# MCU.net
KiCad netlist of a schematic drawn in Altium Designer
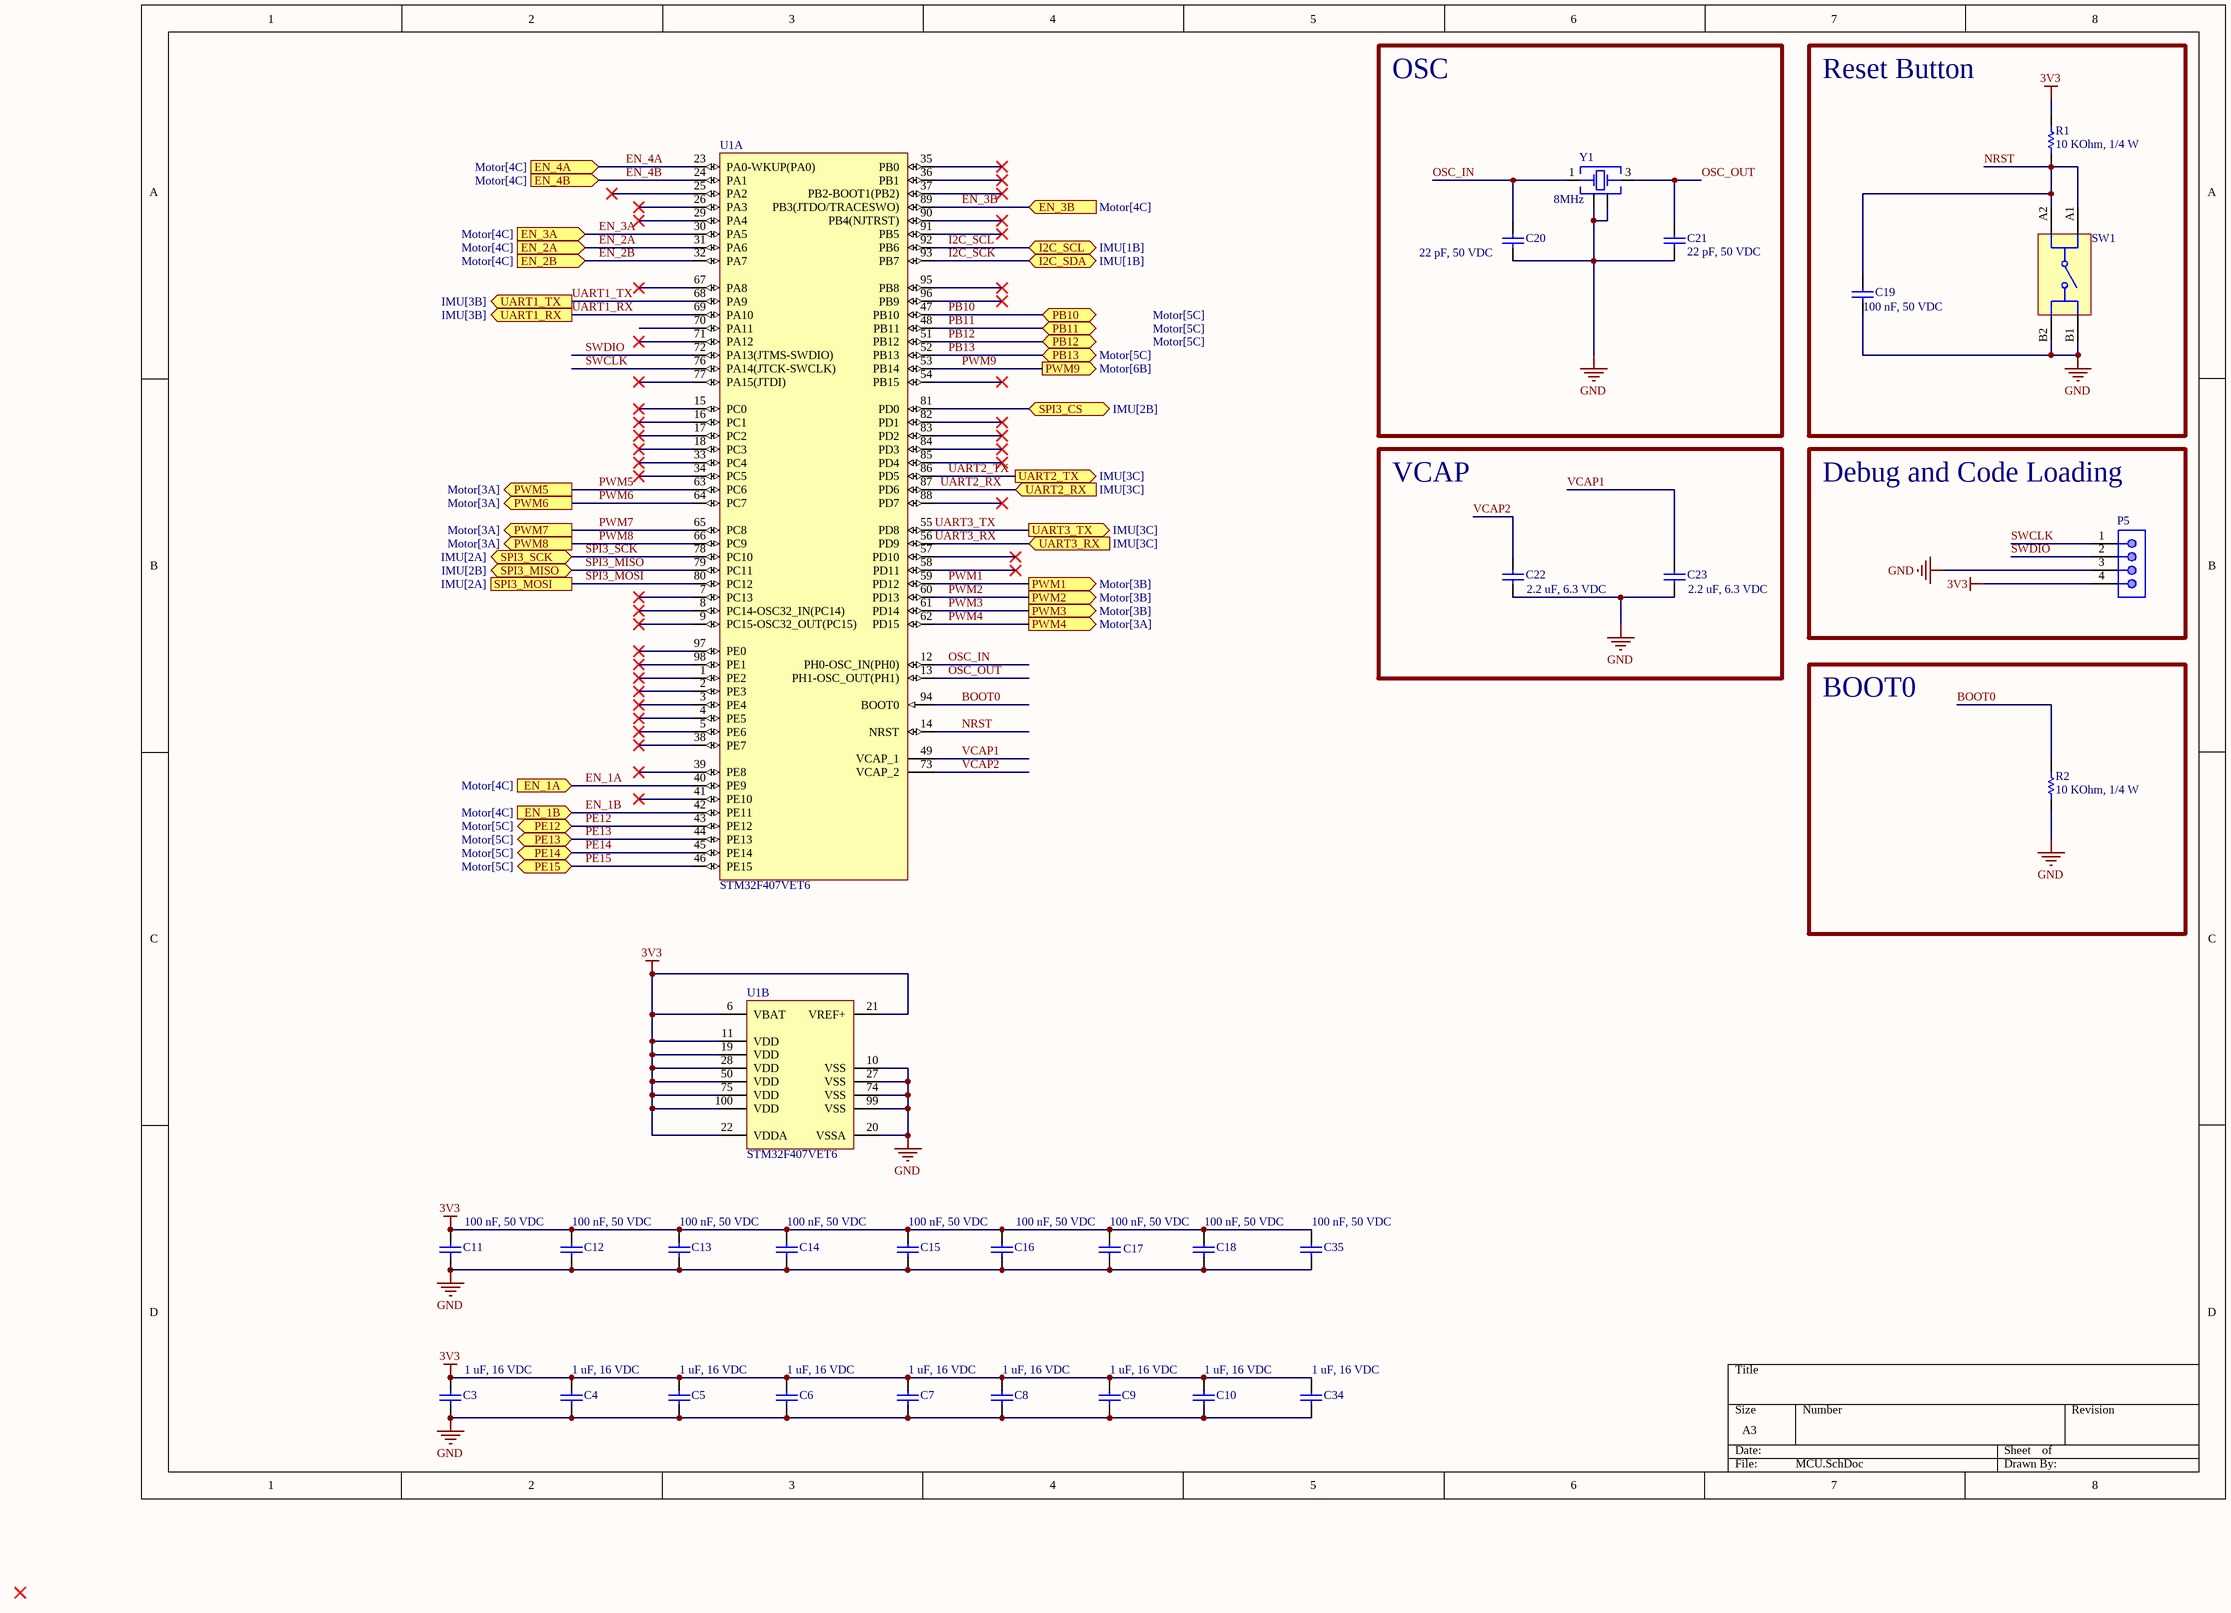
[diagram p0: MCU.SchDoc]

(export (version "E")
  (design (tool "Eeschema 10.0.6"))
  (components
    (comp (ref "C3")
      (value "1 uF, 16 VDC")
      (footprint "CAP_0603")
      (description "CAP, size 0603, 1 uF, 16 VDC")
      (fields (field (name "TOLERANCE") "+/-10%"))
      (libsource (lib "Altium_Ceramic_Cap") (part "0106031051016"))
    )
    (comp (ref "C4")
      (value "1 uF, 16 VDC")
      (footprint "CAP_0603")
      (description "CAP, size 0603, 1 uF, 16 VDC")
      (fields (field (name "TOLERANCE") "+/-10%"))
      (libsource (lib "Altium_Ceramic_Cap") (part "0106031051016"))
    )
    (comp (ref "C5")
      (value "1 uF, 16 VDC")
      (footprint "CAP_0603")
      (description "CAP, size 0603, 1 uF, 16 VDC")
      (fields (field (name "TOLERANCE") "+/-10%"))
      (libsource (lib "Altium_Ceramic_Cap") (part "0106031051016"))
    )
    (comp (ref "C6")
      (value "1 uF, 16 VDC")
      (footprint "CAP_0603")
      (description "CAP, size 0603, 1 uF, 16 VDC")
      (fields (field (name "TOLERANCE") "+/-10%"))
      (libsource (lib "Altium_Ceramic_Cap") (part "0106031051016"))
    )
    (comp (ref "C7")
      (value "1 uF, 16 VDC")
      (footprint "CAP_0603")
      (description "CAP, size 0603, 1 uF, 16 VDC")
      (fields (field (name "TOLERANCE") "+/-10%"))
      (libsource (lib "Altium_Ceramic_Cap") (part "0106031051016"))
    )
    (comp (ref "C8")
      (value "1 uF, 16 VDC")
      (footprint "CAP_0603")
      (description "CAP, size 0603, 1 uF, 16 VDC")
      (fields (field (name "TOLERANCE") "+/-10%"))
      (libsource (lib "Altium_Ceramic_Cap") (part "0106031051016"))
    )
    (comp (ref "C9")
      (value "1 uF, 16 VDC")
      (footprint "CAP_0603")
      (description "CAP, size 0603, 1 uF, 16 VDC")
      (fields (field (name "TOLERANCE") "+/-10%"))
      (libsource (lib "Altium_Ceramic_Cap") (part "0106031051016"))
    )
    (comp (ref "C10")
      (value "1 uF, 16 VDC")
      (footprint "CAP_0603")
      (description "CAP, size 0603, 1 uF, 16 VDC")
      (fields (field (name "TOLERANCE") "+/-10%"))
      (libsource (lib "Altium_Ceramic_Cap") (part "0106031051016"))
    )
    (comp (ref "C11")
      (value "100 nF, 50 VDC")
      (footprint "CAP_0603")
      (description "CAP, size 0603, 100 nF, 50 VDC")
      (fields (field (name "TOLERANCE") "+/-10%"))
      (libsource (lib "Altium_Ceramic_Cap") (part "0106031041050"))
    )
    (comp (ref "C12")
      (value "100 nF, 50 VDC")
      (footprint "CAP_0603")
      (description "CAP, size 0603, 100 nF, 50 VDC")
      (fields (field (name "TOLERANCE") "+/-10%"))
      (libsource (lib "Altium_Ceramic_Cap") (part "0106031041050"))
    )
    (comp (ref "C13")
      (value "100 nF, 50 VDC")
      (footprint "CAP_0603")
      (description "CAP, size 0603, 100 nF, 50 VDC")
      (fields (field (name "TOLERANCE") "+/-10%"))
      (libsource (lib "Altium_Ceramic_Cap") (part "0106031041050"))
    )
    (comp (ref "C14")
      (value "100 nF, 50 VDC")
      (footprint "CAP_0603")
      (description "CAP, size 0603, 100 nF, 50 VDC")
      (fields (field (name "TOLERANCE") "+/-10%"))
      (libsource (lib "Altium_Ceramic_Cap") (part "0106031041050"))
    )
    (comp (ref "C15")
      (value "100 nF, 50 VDC")
      (footprint "CAP_0603")
      (description "CAP, size 0603, 100 nF, 50 VDC")
      (fields (field (name "TOLERANCE") "+/-10%"))
      (libsource (lib "Altium_Ceramic_Cap") (part "0106031041050"))
    )
    (comp (ref "C16")
      (value "100 nF, 50 VDC")
      (footprint "CAP_0603")
      (description "CAP, size 0603, 100 nF, 50 VDC")
      (fields (field (name "TOLERANCE") "+/-10%"))
      (libsource (lib "Altium_Ceramic_Cap") (part "0106031041050"))
    )
    (comp (ref "C17")
      (value "100 nF, 50 VDC")
      (footprint "CAP_0603")
      (description "CAP, size 0603, 100 nF, 50 VDC")
      (fields (field (name "TOLERANCE") "+/-10%"))
      (libsource (lib "Altium_Ceramic_Cap") (part "0106031041050"))
    )
    (comp (ref "C18")
      (value "100 nF, 50 VDC")
      (footprint "CAP_0603")
      (description "CAP, size 0603, 100 nF, 50 VDC")
      (fields (field (name "TOLERANCE") "+/-10%"))
      (libsource (lib "Altium_Ceramic_Cap") (part "0106031041050"))
    )
    (comp (ref "C19")
      (value "100 nF, 50 VDC")
      (footprint "CAP_0603")
      (description "CAP, size 0603, 100 nF, 50 VDC")
      (fields (field (name "TOLERANCE") "+/-10%"))
      (libsource (lib "Altium_Ceramic_Cap") (part "0106031041050"))
    )
    (comp (ref "C20")
      (value "22 pF, 50 VDC")
      (footprint "CAP_0603")
      (description "CAP, size 0603, 22 pF, 50 VDC")
      (fields (field (name "TOLERANCE") "+/-5%"))
      (libsource (lib "Altium_Ceramic_Cap") (part "0106032200550"))
    )
    (comp (ref "C21")
      (value "22 pF, 50 VDC")
      (footprint "CAP_0603")
      (description "CAP, size 0603, 22 pF, 50 VDC")
      (fields (field (name "TOLERANCE") "+/-5%"))
      (libsource (lib "Altium_Ceramic_Cap") (part "0106032200550"))
    )
    (comp (ref "C22")
      (value "2.2 uF, 6.3 VDC")
      (footprint "CAP_0603")
      (description "CAP, size 0603, 2.2 uF, 6.3 VDC")
      (fields (field (name "TOLERANCE") "+/-10%"))
      (libsource (lib "Altium_Ceramic_Cap") (part "010603225106.3"))
    )
    (comp (ref "C23")
      (value "2.2 uF, 6.3 VDC")
      (footprint "CAP_0603")
      (description "CAP, size 0603, 2.2 uF, 6.3 VDC")
      (fields (field (name "TOLERANCE") "+/-10%"))
      (libsource (lib "Altium_Ceramic_Cap") (part "010603225106.3"))
    )
    (comp (ref "C34")
      (value "1 uF, 16 VDC")
      (footprint "CAP_0603")
      (description "CAP, size 0603, 1 uF, 16 VDC")
      (fields (field (name "TOLERANCE") "+/-10%"))
      (libsource (lib "Altium_Ceramic_Cap") (part "0106031051016"))
    )
    (comp (ref "C35")
      (value "100 nF, 50 VDC")
      (footprint "CAP_0603")
      (description "CAP, size 0603, 100 nF, 50 VDC")
      (fields (field (name "TOLERANCE") "+/-10%"))
      (libsource (lib "Altium_Ceramic_Cap") (part "0106031041050"))
    )
    (comp (ref "P5")
      (value "61300411121")
      (footprint "61300411121")
      (description "WR-PHD Pin Header, THT, pitch 2.54mm, Single Row, Vertical, 4p")
      (fields (field (name "MANUFACTURER") "Wurth Elektronik"))
      (libsource (lib "Altium_Header") (part "61300411121"))
    )
    (comp (ref "R1")
      (value "10 KOhm, 1/4 W")
      (footprint "resistor_0603")
      (description "RES, size 0603, 10 KOhm, 1/4 W")
      (libsource (lib "Altium_Resistor") (part "0006031031"))
    )
    (comp (ref "R2")
      (value "10 KOhm, 1/4 W")
      (footprint "resistor_0603")
      (description "RES, size 0603, 10 KOhm, 1/4 W")
      (libsource (lib "Altium_Resistor") (part "0006031031"))
    )
    (comp (ref "SW1")
      (value "430483035816")
      (footprint "WS-TASV_L6W6H3.5_4304x30358x6")
      (description "WS-TASV J-Bend SMT Washable Tact Switch, 12VDC, 50mA, 160g, height 3.5mm")
      (fields (field (name "MANUFACTURER") "Wurth Elektronik"))
      (libsource (lib "Board_C24") (part "430483035816"))
    )
    (comp (ref "U1")
      (value "STM32F407VET6")
      (footprint "STM-LQFP100_V")
      (fields (field (name "MANUFACTURER") "STMicroelectronics"))
      (libsource (lib "Altium Content Vault") (part "MC-ARM-STM32F40X_41X-SQ100"))
    )
    (comp (ref "Y1")
      (value "8MHz")
      (footprint "WE-XTAL_CFPX-104")
      (description "WE-XTAL Quartz Crystal, SMT, CFPX-104, 8MHz, +/-20ppm")
      (fields
        (field (name "MANUFACTURER PART NUMBER") "830106162701")
        (field (name "MANUFACTURER") "Wurth Elektronik")
      )
      (libsource (lib "Board_C24") (part "830106162701"))
    )
  )
  (nets
    (net (code "1") (name "/BOOT0") (class "Default")
      (node (ref "R2") (pin "2") (pinfunction "2_2") (pintype "passive"))
      (node (ref "U1") (pin "94") (pinfunction "BOOT0_94") (pintype "input"))
    )
    (net (code "2") (name "/EN_1A") (class "Default")
      (node (ref "U1") (pin "40") (pinfunction "PE9_40") (pintype "bidirectional"))
    )
    (net (code "3") (name "/EN_1B") (class "Default")
      (node (ref "U1") (pin "42") (pinfunction "PE11_42") (pintype "bidirectional"))
    )
    (net (code "4") (name "/EN_2A") (class "Default")
      (node (ref "U1") (pin "31") (pinfunction "PA6_31") (pintype "bidirectional"))
    )
    (net (code "5") (name "/EN_2B") (class "Default")
      (node (ref "U1") (pin "32") (pinfunction "PA7_32") (pintype "bidirectional"))
    )
    (net (code "6") (name "/EN_3A") (class "Default")
      (node (ref "U1") (pin "30") (pinfunction "PA5_30") (pintype "bidirectional"))
    )
    (net (code "7") (name "/EN_3B") (class "Default")
      (node (ref "U1") (pin "89") (pinfunction "PB3(JTDO/TRACESWO)_89") (pintype "bidirectional"))
    )
    (net (code "8") (name "/EN_4A") (class "Default")
      (node (ref "U1") (pin "23") (pinfunction "PA0-WKUP(PA0)_23") (pintype "bidirectional"))
    )
    (net (code "9") (name "/EN_4B") (class "Default")
      (node (ref "U1") (pin "24") (pinfunction "PA1_24") (pintype "bidirectional"))
    )
    (net (code "10") (name "/I2C_SCK") (class "Default")
      (node (ref "U1") (pin "93") (pinfunction "PB7_93") (pintype "bidirectional"))
    )
    (net (code "11") (name "/I2C_SCL") (class "Default")
      (node (ref "U1") (pin "92") (pinfunction "PB6_92") (pintype "bidirectional"))
    )
    (net (code "12") (name "/NRST") (class "Default")
      (node (ref "C19") (pin "2") (pinfunction "2_2") (pintype "passive"))
      (node (ref "R1") (pin "1") (pinfunction "1_1") (pintype "passive"))
      (node (ref "SW1") (pin "A1") (pinfunction "A1_A1") (pintype "passive"))
      (node (ref "SW1") (pin "A2") (pinfunction "A2_A2") (pintype "passive"))
      (node (ref "U1") (pin "14") (pinfunction "NRST_14") (pintype "bidirectional"))
    )
    (net (code "13") (name "/OSC_IN") (class "Default")
      (node (ref "C20") (pin "2") (pinfunction "2_2") (pintype "passive"))
      (node (ref "U1") (pin "12") (pinfunction "PH0-OSC_IN(PH0)_12") (pintype "bidirectional"))
      (node (ref "Y1") (pin "1") (pinfunction "OSC1_1") (pintype "passive"))
    )
    (net (code "14") (name "/OSC_OUT") (class "Default")
      (node (ref "C21") (pin "2") (pinfunction "2_2") (pintype "passive"))
      (node (ref "U1") (pin "13") (pinfunction "PH1-OSC_OUT(PH1)_13") (pintype "bidirectional"))
      (node (ref "Y1") (pin "3") (pinfunction "OSC2_3") (pintype "passive"))
    )
    (net (code "15") (name "/PB10") (class "Default")
      (node (ref "U1") (pin "47") (pinfunction "PB10_47") (pintype "bidirectional"))
    )
    (net (code "16") (name "/PB11") (class "Default")
      (node (ref "U1") (pin "48") (pinfunction "PB11_48") (pintype "bidirectional"))
    )
    (net (code "17") (name "/PB12") (class "Default")
      (node (ref "U1") (pin "51") (pinfunction "PB12_51") (pintype "bidirectional"))
    )
    (net (code "18") (name "/PB13") (class "Default")
      (node (ref "U1") (pin "52") (pinfunction "PB13_52") (pintype "bidirectional"))
    )
    (net (code "19") (name "/PE12") (class "Default")
      (node (ref "U1") (pin "43") (pinfunction "PE12_43") (pintype "bidirectional"))
    )
    (net (code "20") (name "/PE13") (class "Default")
      (node (ref "U1") (pin "44") (pinfunction "PE13_44") (pintype "bidirectional"))
    )
    (net (code "21") (name "/PE14") (class "Default")
      (node (ref "U1") (pin "45") (pinfunction "PE14_45") (pintype "bidirectional"))
    )
    (net (code "22") (name "/PE15") (class "Default")
      (node (ref "U1") (pin "46") (pinfunction "PE15_46") (pintype "bidirectional"))
    )
    (net (code "23") (name "/PWM1") (class "Default")
      (node (ref "U1") (pin "59") (pinfunction "PD12_59") (pintype "bidirectional"))
    )
    (net (code "24") (name "/PWM2") (class "Default")
      (node (ref "U1") (pin "60") (pinfunction "PD13_60") (pintype "bidirectional"))
    )
    (net (code "25") (name "/PWM3") (class "Default")
      (node (ref "U1") (pin "61") (pinfunction "PD14_61") (pintype "bidirectional"))
    )
    (net (code "26") (name "/PWM4") (class "Default")
      (node (ref "U1") (pin "62") (pinfunction "PD15_62") (pintype "bidirectional"))
    )
    (net (code "27") (name "/PWM5") (class "Default")
      (node (ref "U1") (pin "63") (pinfunction "PC6_63") (pintype "bidirectional"))
    )
    (net (code "28") (name "/PWM6") (class "Default")
      (node (ref "U1") (pin "64") (pinfunction "PC7_64") (pintype "bidirectional"))
    )
    (net (code "29") (name "/PWM7") (class "Default")
      (node (ref "U1") (pin "65") (pinfunction "PC8_65") (pintype "bidirectional"))
    )
    (net (code "30") (name "/PWM8") (class "Default")
      (node (ref "U1") (pin "66") (pinfunction "PC9_66") (pintype "bidirectional"))
    )
    (net (code "31") (name "/PWM9") (class "Default")
      (node (ref "U1") (pin "53") (pinfunction "PB14_53") (pintype "bidirectional"))
    )
    (net (code "32") (name "/SPI3_CS") (class "Default")
      (node (ref "U1") (pin "81") (pinfunction "PD0_81") (pintype "bidirectional"))
    )
    (net (code "33") (name "/SPI3_MISO") (class "Default")
      (node (ref "U1") (pin "79") (pinfunction "PC11_79") (pintype "bidirectional"))
    )
    (net (code "34") (name "/SPI3_MOSI") (class "Default")
      (node (ref "U1") (pin "80") (pinfunction "PC12_80") (pintype "bidirectional"))
    )
    (net (code "35") (name "/SPI3_SCK") (class "Default")
      (node (ref "U1") (pin "78") (pinfunction "PC10_78") (pintype "bidirectional"))
    )
    (net (code "36") (name "/SWCLK") (class "Default")
      (node (ref "P5") (pin "1") (pinfunction "1_1") (pintype "passive"))
      (node (ref "U1") (pin "76") (pinfunction "PA14(JTCK-SWCLK)_76") (pintype "bidirectional"))
    )
    (net (code "37") (name "/SWDIO") (class "Default")
      (node (ref "P5") (pin "2") (pinfunction "2_2") (pintype "passive"))
      (node (ref "U1") (pin "72") (pinfunction "PA13(JTMS-SWDIO)_72") (pintype "bidirectional"))
    )
    (net (code "38") (name "/UART1_RX") (class "Default")
      (node (ref "U1") (pin "69") (pinfunction "PA10_69") (pintype "bidirectional"))
    )
    (net (code "39") (name "/UART1_TX") (class "Default")
      (node (ref "U1") (pin "68") (pinfunction "PA9_68") (pintype "bidirectional"))
    )
    (net (code "40") (name "/UART2_RX") (class "Default")
      (node (ref "U1") (pin "87") (pinfunction "PD6_87") (pintype "bidirectional"))
    )
    (net (code "41") (name "/UART2_TX") (class "Default")
      (node (ref "U1") (pin "86") (pinfunction "PD5_86") (pintype "bidirectional"))
    )
    (net (code "42") (name "/UART3_RX") (class "Default")
      (node (ref "U1") (pin "56") (pinfunction "PD9_56") (pintype "bidirectional"))
    )
    (net (code "43") (name "/UART3_TX") (class "Default")
      (node (ref "U1") (pin "55") (pinfunction "PD8_55") (pintype "bidirectional"))
    )
    (net (code "44") (name "/VCAP1") (class "Default")
      (node (ref "C23") (pin "2") (pinfunction "2_2") (pintype "passive"))
      (node (ref "U1") (pin "49") (pinfunction "VCAP_1_49") (pintype "power_in"))
    )
    (net (code "45") (name "/VCAP2") (class "Default")
      (node (ref "C22") (pin "2") (pinfunction "2_2") (pintype "passive"))
      (node (ref "U1") (pin "73") (pinfunction "VCAP_2_73") (pintype "power_in"))
    )
    (net (code "46") (name "3V3") (class "Default")
      (node (ref "C10") (pin "2") (pinfunction "2_2") (pintype "passive"))
      (node (ref "C11") (pin "2") (pinfunction "2_2") (pintype "passive"))
      (node (ref "C12") (pin "2") (pinfunction "2_2") (pintype "passive"))
      (node (ref "C13") (pin "2") (pinfunction "2_2") (pintype "passive"))
      (node (ref "C14") (pin "2") (pinfunction "2_2") (pintype "passive"))
      (node (ref "C15") (pin "2") (pinfunction "2_2") (pintype "passive"))
      (node (ref "C16") (pin "2") (pinfunction "2_2") (pintype "passive"))
      (node (ref "C17") (pin "2") (pinfunction "2_2") (pintype "passive"))
      (node (ref "C18") (pin "2") (pinfunction "2_2") (pintype "passive"))
      (node (ref "C3") (pin "2") (pinfunction "2_2") (pintype "passive"))
      (node (ref "C34") (pin "2") (pinfunction "2_2") (pintype "passive"))
      (node (ref "C35") (pin "2") (pinfunction "2_2") (pintype "passive"))
      (node (ref "C4") (pin "2") (pinfunction "2_2") (pintype "passive"))
      (node (ref "C5") (pin "2") (pinfunction "2_2") (pintype "passive"))
      (node (ref "C6") (pin "2") (pinfunction "2_2") (pintype "passive"))
      (node (ref "C7") (pin "2") (pinfunction "2_2") (pintype "passive"))
      (node (ref "C8") (pin "2") (pinfunction "2_2") (pintype "passive"))
      (node (ref "C9") (pin "2") (pinfunction "2_2") (pintype "passive"))
      (node (ref "P5") (pin "4") (pinfunction "4_4") (pintype "passive"))
      (node (ref "R1") (pin "2") (pinfunction "2_2") (pintype "passive"))
      (node (ref "U1") (pin "100") (pinfunction "VDD_100") (pintype "power_in"))
      (node (ref "U1") (pin "11") (pinfunction "VDD_11") (pintype "power_in"))
      (node (ref "U1") (pin "19") (pinfunction "VDD_19") (pintype "power_in"))
      (node (ref "U1") (pin "21") (pinfunction "VREF+_21") (pintype "power_in"))
      (node (ref "U1") (pin "22") (pinfunction "VDDA_22") (pintype "power_in"))
      (node (ref "U1") (pin "28") (pinfunction "VDD_28") (pintype "power_in"))
      (node (ref "U1") (pin "50") (pinfunction "VDD_50") (pintype "power_in"))
      (node (ref "U1") (pin "6") (pinfunction "VBAT_6") (pintype "power_in"))
      (node (ref "U1") (pin "75") (pinfunction "VDD_75") (pintype "power_in"))
    )
    (net (code "47") (name "GND") (class "Default")
      (node (ref "C10") (pin "1") (pinfunction "1_1") (pintype "passive"))
      (node (ref "C11") (pin "1") (pinfunction "1_1") (pintype "passive"))
      (node (ref "C12") (pin "1") (pinfunction "1_1") (pintype "passive"))
      (node (ref "C13") (pin "1") (pinfunction "1_1") (pintype "passive"))
      (node (ref "C14") (pin "1") (pinfunction "1_1") (pintype "passive"))
      (node (ref "C15") (pin "1") (pinfunction "1_1") (pintype "passive"))
      (node (ref "C16") (pin "1") (pinfunction "1_1") (pintype "passive"))
      (node (ref "C17") (pin "1") (pinfunction "1_1") (pintype "passive"))
      (node (ref "C18") (pin "1") (pinfunction "1_1") (pintype "passive"))
      (node (ref "C19") (pin "1") (pinfunction "1_1") (pintype "passive"))
      (node (ref "C20") (pin "1") (pinfunction "1_1") (pintype "passive"))
      (node (ref "C21") (pin "1") (pinfunction "1_1") (pintype "passive"))
      (node (ref "C22") (pin "1") (pinfunction "1_1") (pintype "passive"))
      (node (ref "C23") (pin "1") (pinfunction "1_1") (pintype "passive"))
      (node (ref "C3") (pin "1") (pinfunction "1_1") (pintype "passive"))
      (node (ref "C34") (pin "1") (pinfunction "1_1") (pintype "passive"))
      (node (ref "C35") (pin "1") (pinfunction "1_1") (pintype "passive"))
      (node (ref "C4") (pin "1") (pinfunction "1_1") (pintype "passive"))
      (node (ref "C5") (pin "1") (pinfunction "1_1") (pintype "passive"))
      (node (ref "C6") (pin "1") (pinfunction "1_1") (pintype "passive"))
      (node (ref "C7") (pin "1") (pinfunction "1_1") (pintype "passive"))
      (node (ref "C8") (pin "1") (pinfunction "1_1") (pintype "passive"))
      (node (ref "C9") (pin "1") (pinfunction "1_1") (pintype "passive"))
      (node (ref "P5") (pin "3") (pinfunction "3_3") (pintype "passive"))
      (node (ref "R2") (pin "1") (pinfunction "1_1") (pintype "passive"))
      (node (ref "SW1") (pin "B1") (pinfunction "B1_B1") (pintype "passive"))
      (node (ref "SW1") (pin "B2") (pinfunction "B2_B2") (pintype "passive"))
      (node (ref "U1") (pin "10") (pinfunction "VSS_10") (pintype "power_in"))
      (node (ref "U1") (pin "20") (pinfunction "VSSA_20") (pintype "power_in"))
      (node (ref "U1") (pin "27") (pinfunction "VSS_27") (pintype "power_in"))
      (node (ref "U1") (pin "74") (pinfunction "VSS_74") (pintype "power_in"))
      (node (ref "U1") (pin "99") (pinfunction "VSS_99") (pintype "power_in"))
      (node (ref "Y1") (pin "2") (pinfunction "GND_2") (pintype "passive"))
      (node (ref "Y1") (pin "4") (pinfunction "GND_4") (pintype "passive"))
    )
    (net (code "48") (name "unconnected-(U1A-PA2-Pad25)") (class "Default")
      (node (ref "U1") (pin "25") (pinfunction "PA2_25") (pintype "bidirectional+no_connect"))
    )
    (net (code "49") (name "unconnected-(U1A-PA3-Pad26)") (class "Default")
      (node (ref "U1") (pin "26") (pinfunction "PA3_26") (pintype "bidirectional+no_connect"))
    )
    (net (code "50") (name "unconnected-(U1A-PA4-Pad29)") (class "Default")
      (node (ref "U1") (pin "29") (pinfunction "PA4_29") (pintype "bidirectional+no_connect"))
    )
    (net (code "51") (name "unconnected-(U1A-PA8-Pad67)") (class "Default")
      (node (ref "U1") (pin "67") (pinfunction "PA8_67") (pintype "bidirectional+no_connect"))
    )
    (net (code "52") (name "unconnected-(U1A-PA11-Pad70)") (class "Default")
      (node (ref "U1") (pin "70") (pinfunction "PA11_70") (pintype "bidirectional"))
    )
    (net (code "53") (name "unconnected-(U1A-PA12-Pad71)") (class "Default")
      (node (ref "U1") (pin "71") (pinfunction "PA12_71") (pintype "bidirectional+no_connect"))
    )
    (net (code "54") (name "unconnected-(U1A-PA15(JTDI)-Pad77)") (class "Default")
      (node (ref "U1") (pin "77") (pinfunction "PA15(JTDI)_77") (pintype "bidirectional+no_connect"))
    )
    (net (code "55") (name "unconnected-(U1A-PB0-Pad35)") (class "Default")
      (node (ref "U1") (pin "35") (pinfunction "PB0_35") (pintype "bidirectional+no_connect"))
    )
    (net (code "56") (name "unconnected-(U1A-PB1-Pad36)") (class "Default")
      (node (ref "U1") (pin "36") (pinfunction "PB1_36") (pintype "bidirectional+no_connect"))
    )
    (net (code "57") (name "unconnected-(U1A-PB2-BOOT1(PB2)-Pad37)") (class "Default")
      (node (ref "U1") (pin "37") (pinfunction "PB2-BOOT1(PB2)_37") (pintype "bidirectional+no_connect"))
    )
    (net (code "58") (name "unconnected-(U1A-PB4(NJTRST)-Pad90)") (class "Default")
      (node (ref "U1") (pin "90") (pinfunction "PB4(NJTRST)_90") (pintype "bidirectional+no_connect"))
    )
    (net (code "59") (name "unconnected-(U1A-PB5-Pad91)") (class "Default")
      (node (ref "U1") (pin "91") (pinfunction "PB5_91") (pintype "bidirectional+no_connect"))
    )
    (net (code "60") (name "unconnected-(U1A-PB8-Pad95)") (class "Default")
      (node (ref "U1") (pin "95") (pinfunction "PB8_95") (pintype "bidirectional+no_connect"))
    )
    (net (code "61") (name "unconnected-(U1A-PB9-Pad96)") (class "Default")
      (node (ref "U1") (pin "96") (pinfunction "PB9_96") (pintype "bidirectional+no_connect"))
    )
    (net (code "62") (name "unconnected-(U1A-PB15-Pad54)") (class "Default")
      (node (ref "U1") (pin "54") (pinfunction "PB15_54") (pintype "bidirectional+no_connect"))
    )
    (net (code "63") (name "unconnected-(U1A-PC0-Pad15)") (class "Default")
      (node (ref "U1") (pin "15") (pinfunction "PC0_15") (pintype "bidirectional+no_connect"))
    )
    (net (code "64") (name "unconnected-(U1A-PC1-Pad16)") (class "Default")
      (node (ref "U1") (pin "16") (pinfunction "PC1_16") (pintype "bidirectional+no_connect"))
    )
    (net (code "65") (name "unconnected-(U1A-PC2-Pad17)") (class "Default")
      (node (ref "U1") (pin "17") (pinfunction "PC2_17") (pintype "bidirectional+no_connect"))
    )
    (net (code "66") (name "unconnected-(U1A-PC3-Pad18)") (class "Default")
      (node (ref "U1") (pin "18") (pinfunction "PC3_18") (pintype "bidirectional+no_connect"))
    )
    (net (code "67") (name "unconnected-(U1A-PC4-Pad33)") (class "Default")
      (node (ref "U1") (pin "33") (pinfunction "PC4_33") (pintype "bidirectional+no_connect"))
    )
    (net (code "68") (name "unconnected-(U1A-PC5-Pad34)") (class "Default")
      (node (ref "U1") (pin "34") (pinfunction "PC5_34") (pintype "bidirectional+no_connect"))
    )
    (net (code "69") (name "unconnected-(U1A-PC13-Pad7)") (class "Default")
      (node (ref "U1") (pin "7") (pinfunction "PC13_7") (pintype "bidirectional+no_connect"))
    )
    (net (code "70") (name "unconnected-(U1A-PC14-OSC32_IN(PC14)-Pad8)") (class "Default")
      (node (ref "U1") (pin "8") (pinfunction "PC14-OSC32_IN(PC14)_8") (pintype "bidirectional+no_connect"))
    )
    (net (code "71") (name "unconnected-(U1A-PC15-OSC32_OUT(PC15)-Pad9)") (class "Default")
      (node (ref "U1") (pin "9") (pinfunction "PC15-OSC32_OUT(PC15)_9") (pintype "bidirectional+no_connect"))
    )
    (net (code "72") (name "unconnected-(U1A-PD1-Pad82)") (class "Default")
      (node (ref "U1") (pin "82") (pinfunction "PD1_82") (pintype "bidirectional+no_connect"))
    )
    (net (code "73") (name "unconnected-(U1A-PD2-Pad83)") (class "Default")
      (node (ref "U1") (pin "83") (pinfunction "PD2_83") (pintype "bidirectional+no_connect"))
    )
    (net (code "74") (name "unconnected-(U1A-PD3-Pad84)") (class "Default")
      (node (ref "U1") (pin "84") (pinfunction "PD3_84") (pintype "bidirectional+no_connect"))
    )
    (net (code "75") (name "unconnected-(U1A-PD4-Pad85)") (class "Default")
      (node (ref "U1") (pin "85") (pinfunction "PD4_85") (pintype "bidirectional+no_connect"))
    )
    (net (code "76") (name "unconnected-(U1A-PD7-Pad88)") (class "Default")
      (node (ref "U1") (pin "88") (pinfunction "PD7_88") (pintype "bidirectional+no_connect"))
    )
    (net (code "77") (name "unconnected-(U1A-PD10-Pad57)") (class "Default")
      (node (ref "U1") (pin "57") (pinfunction "PD10_57") (pintype "bidirectional+no_connect"))
    )
    (net (code "78") (name "unconnected-(U1A-PD11-Pad58)") (class "Default")
      (node (ref "U1") (pin "58") (pinfunction "PD11_58") (pintype "bidirectional+no_connect"))
    )
    (net (code "79") (name "unconnected-(U1A-PE0-Pad97)") (class "Default")
      (node (ref "U1") (pin "97") (pinfunction "PE0_97") (pintype "bidirectional+no_connect"))
    )
    (net (code "80") (name "unconnected-(U1A-PE1-Pad98)") (class "Default")
      (node (ref "U1") (pin "98") (pinfunction "PE1_98") (pintype "bidirectional+no_connect"))
    )
    (net (code "81") (name "unconnected-(U1A-PE2-Pad1)") (class "Default")
      (node (ref "U1") (pin "1") (pinfunction "PE2_1") (pintype "bidirectional+no_connect"))
    )
    (net (code "82") (name "unconnected-(U1A-PE3-Pad2)") (class "Default")
      (node (ref "U1") (pin "2") (pinfunction "PE3_2") (pintype "bidirectional+no_connect"))
    )
    (net (code "83") (name "unconnected-(U1A-PE4-Pad3)") (class "Default")
      (node (ref "U1") (pin "3") (pinfunction "PE4_3") (pintype "bidirectional+no_connect"))
    )
    (net (code "84") (name "unconnected-(U1A-PE5-Pad4)") (class "Default")
      (node (ref "U1") (pin "4") (pinfunction "PE5_4") (pintype "bidirectional+no_connect"))
    )
    (net (code "85") (name "unconnected-(U1A-PE6-Pad5)") (class "Default")
      (node (ref "U1") (pin "5") (pinfunction "PE6_5") (pintype "bidirectional+no_connect"))
    )
    (net (code "86") (name "unconnected-(U1A-PE7-Pad38)") (class "Default")
      (node (ref "U1") (pin "38") (pinfunction "PE7_38") (pintype "bidirectional+no_connect"))
    )
    (net (code "87") (name "unconnected-(U1A-PE8-Pad39)") (class "Default")
      (node (ref "U1") (pin "39") (pinfunction "PE8_39") (pintype "bidirectional+no_connect"))
    )
    (net (code "88") (name "unconnected-(U1A-PE10-Pad41)") (class "Default")
      (node (ref "U1") (pin "41") (pinfunction "PE10_41") (pintype "bidirectional+no_connect"))
    )
  )
)
